# STM32_Rauch_001.net
KiCad netlist of a schematic drawn in EAGLE
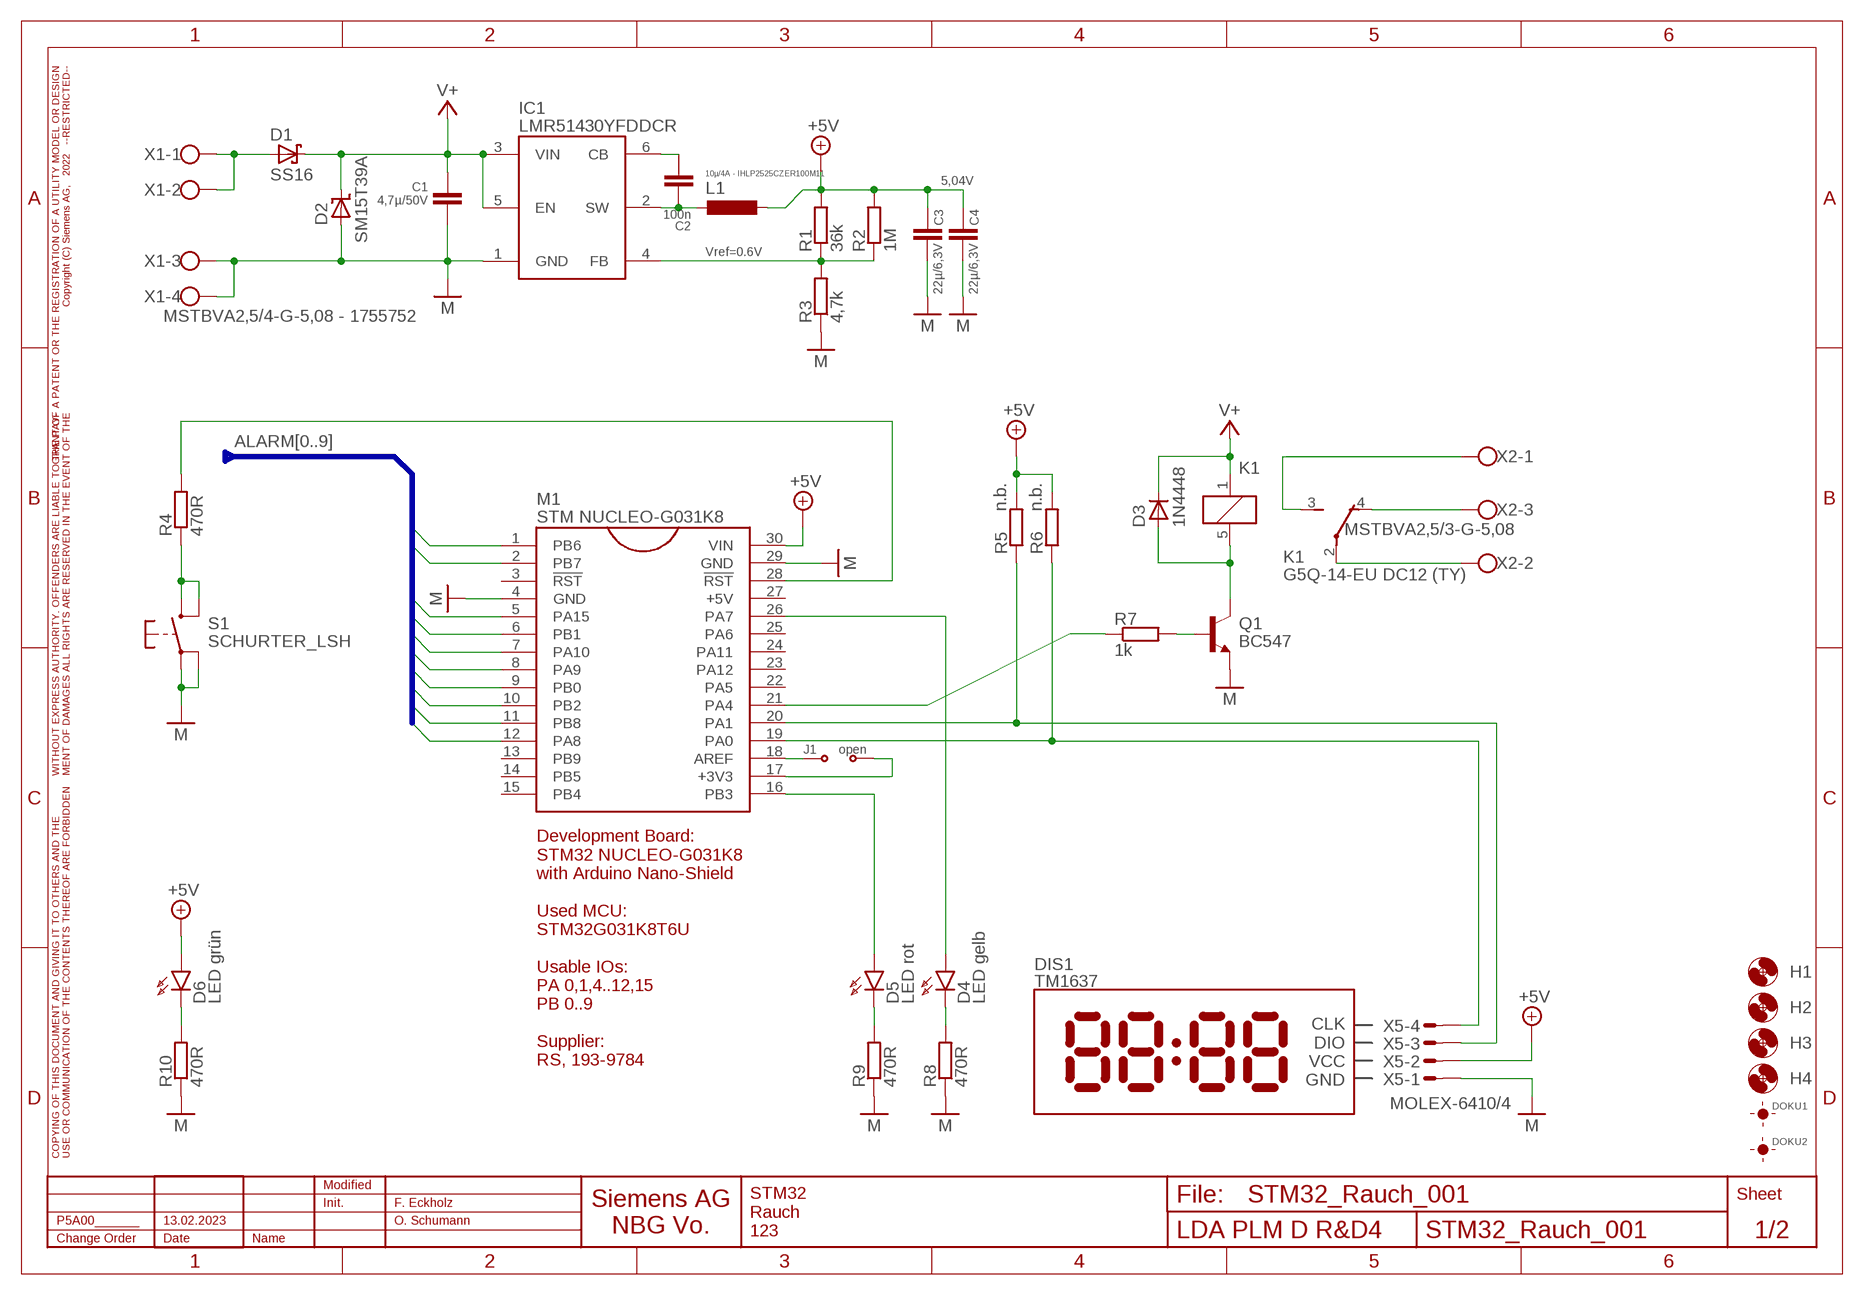
[diagram p0: schematic, sheet 1]
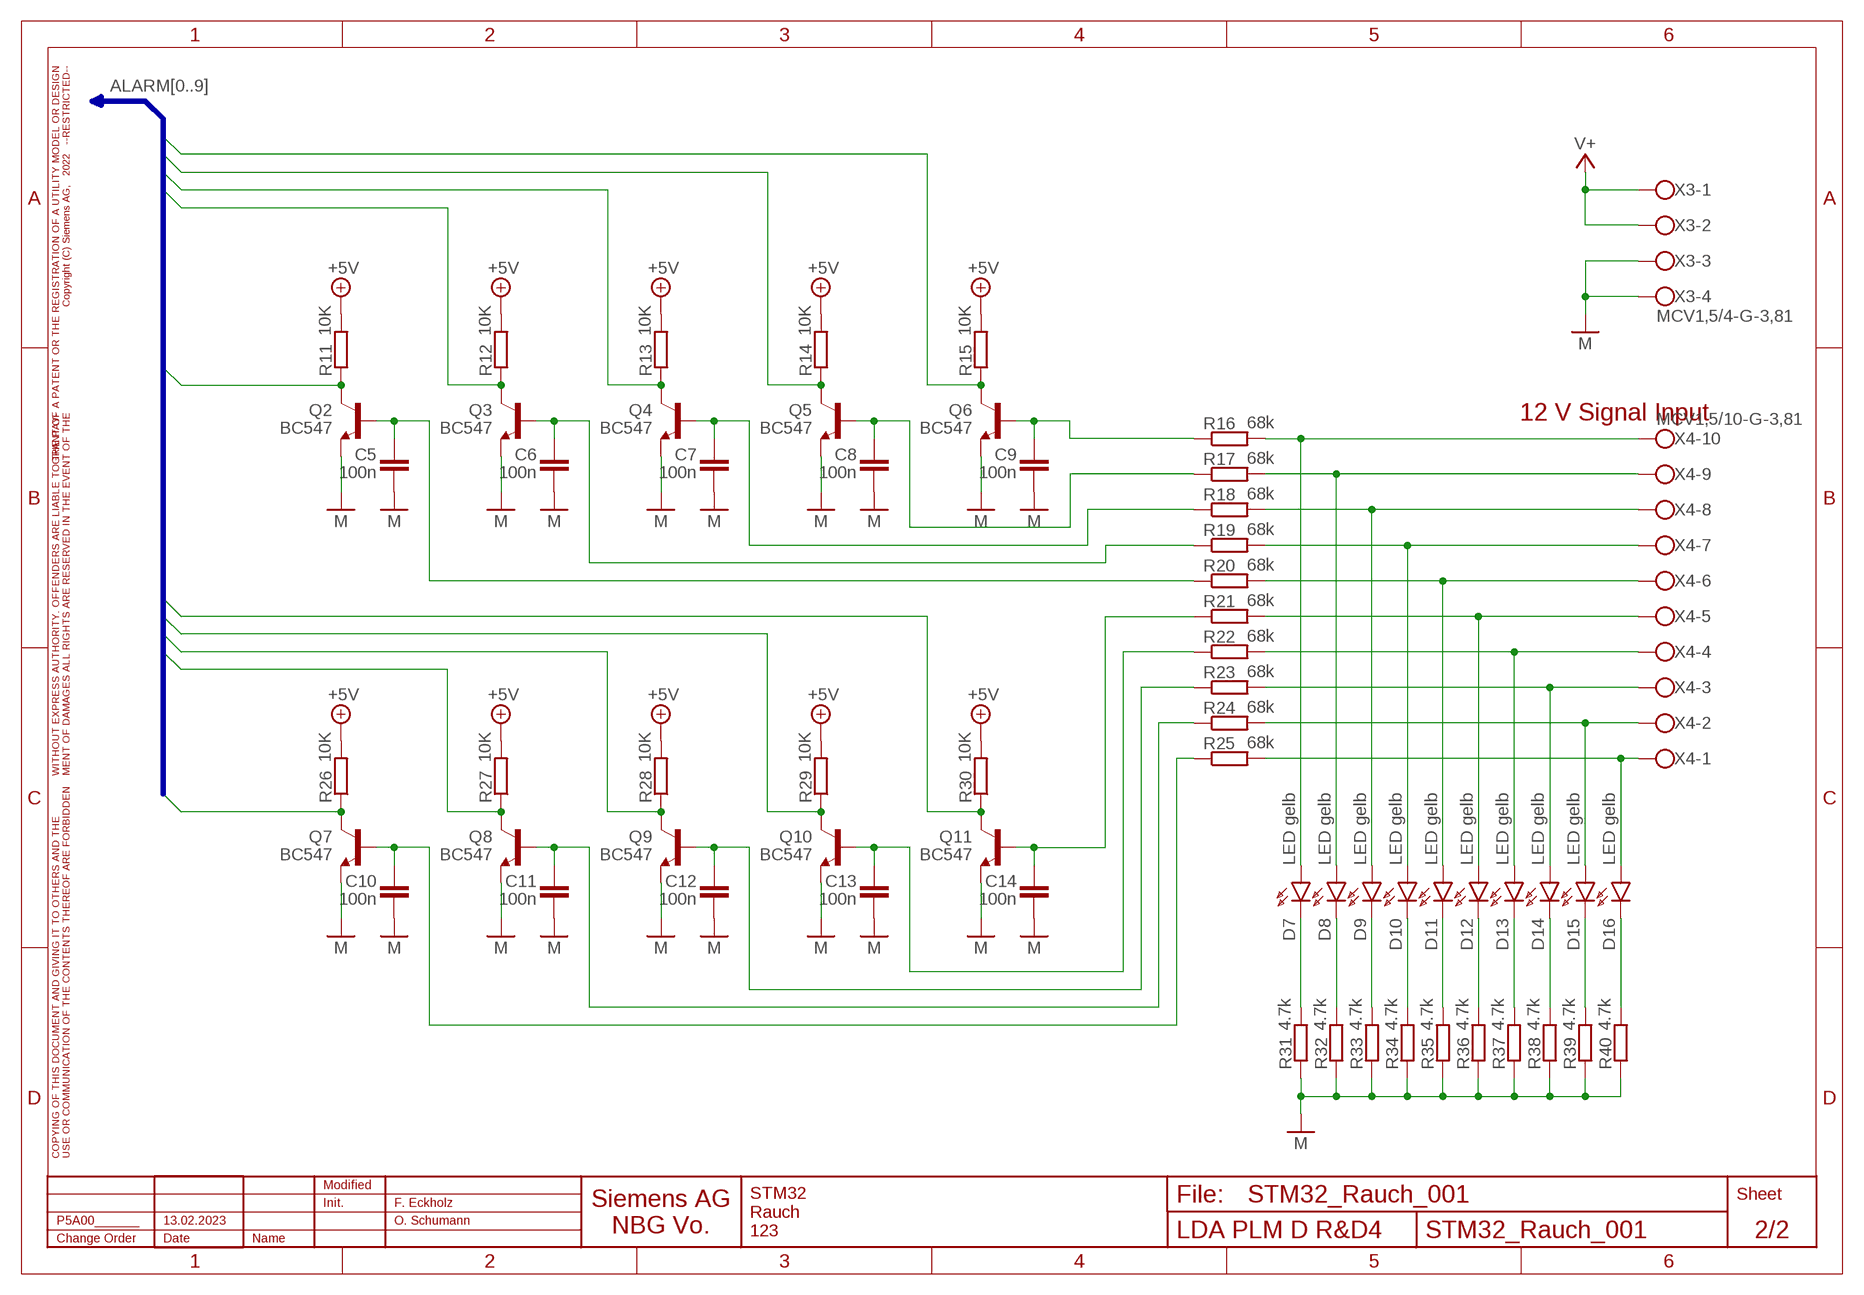
[diagram p1: schematic, sheet 2]

(export (version "E")
  (design (tool "Eeschema 10.0.6"))
  (components
    (comp (ref "C1")
      (value "4,7µ/50V")
      (footprint "eagle-import:CAPC1210")
      (libsource (lib "eagle-import") (part "C-EU1210"))
    )
    (comp (ref "C2")
      (value "100n")
      (footprint "eagle-import:CAPC0603")
      (libsource (lib "eagle-import") (part "C-EU0603"))
    )
    (comp (ref "C3")
      (value "22µ/6,3V")
      (footprint "eagle-import:CAPC1206")
      (libsource (lib "eagle-import") (part "C-EU1206"))
    )
    (comp (ref "C4")
      (value "22µ/6,3V")
      (footprint "eagle-import:CAPC1206")
      (libsource (lib "eagle-import") (part "C-EU1206"))
    )
    (comp (ref "D1")
      (value "SS16")
      (footprint "eagle-import:DIOM-SMA")
      (libsource (lib "eagle-import") (part "DIODE-SCHOTTKY-SMA"))
    )
    (comp (ref "D2")
      (value "SM15T39A")
      (footprint "eagle-import:DIOM-SMC")
      (libsource (lib "eagle-import") (part "DIODE-TVS-UNI-SMC"))
    )
    (comp (ref "D3")
      (value "1N4448")
      (footprint "eagle-import:SOD323")
      (libsource (lib "eagle-import") (part "DIODE-SOD323"))
    )
    (comp (ref "D4")
      (value "LED gelb")
      (footprint "eagle-import:LEDC1608")
      (libsource (lib "eagle-import") (part "DIODE-LED-C1608"))
    )
    (comp (ref "D5")
      (value "LED rot")
      (footprint "eagle-import:LEDC1608")
      (libsource (lib "eagle-import") (part "DIODE-LED-C1608"))
    )
    (comp (ref "D6")
      (value "LED grün")
      (footprint "eagle-import:LEDC1608")
      (libsource (lib "eagle-import") (part "DIODE-LED-C1608"))
    )
    (comp (ref "DIS1")
      (value "TM1637")
      (footprint "eagle-import:TM1637")
      (libsource (lib "eagle-import") (part "TM1637"))
    )
    (comp (ref "DOKU1")
      (value "PAD-FIDU-R200")
      (footprint "eagle-import:FIDU_RUND-2MM")
      (libsource (lib "eagle-import") (part "PAD-FIDU-R200"))
    )
    (comp (ref "DOKU2")
      (value "PAD-FIDU-R200")
      (footprint "eagle-import:FIDU_RUND-2MM")
      (libsource (lib "eagle-import") (part "PAD-FIDU-R200"))
    )
    (comp (ref "DOKU4")
      (value "STM32_Rauch_001")
      (footprint "eagle-import:DOKU-50-TOP")
      (libsource (lib "eagle-import") (part "TEXT-50-TOP"))
    )
    (comp (ref "H1")
      (value "MOUNT-HOLE-3.2")
      (footprint "eagle-import:MOUNT-HOLE-3,2")
      (libsource (lib "eagle-import") (part "MOUNT-HOLE-3.2"))
    )
    (comp (ref "H2")
      (value "MOUNT-HOLE-3.2")
      (footprint "eagle-import:MOUNT-HOLE-3,2")
      (libsource (lib "eagle-import") (part "MOUNT-HOLE-3.2"))
    )
    (comp (ref "H3")
      (value "MOUNT-HOLE-3.2")
      (footprint "eagle-import:MOUNT-HOLE-3,2")
      (libsource (lib "eagle-import") (part "MOUNT-HOLE-3.2"))
    )
    (comp (ref "H4")
      (value "MOUNT-HOLE-3.2")
      (footprint "eagle-import:MOUNT-HOLE-3,2")
      (libsource (lib "eagle-import") (part "MOUNT-HOLE-3.2"))
    )
    (comp (ref "IC1")
      (value "LMR51430YFDDCR")
      (footprint "eagle-import:SOT23-6")
      (libsource (lib "eagle-import") (part "LMR51430"))
    )
    (comp (ref "J1")
      (value "open")
      (footprint "eagle-import:CON-SOLDERJUMPER")
      (libsource (lib "eagle-import") (part "CON-J2D"))
    )
    (comp (ref "K1")
      (value "G5Q-14-EU DC12 (TY)")
      (footprint "eagle-import:OMRON-G5Q")
      (libsource (lib "eagle-import") (part "RELAIS1-OMRON-G5Q"))
    )
    (comp (ref "L1")
      (value "10µ/4A - IHLP2525CZER100M11")
      (footprint "eagle-import:INDM0707")
      (libsource (lib "eagle-import") (part "L-EU0707"))
    )
    (comp (ref "M1")
      (value "STM NUCLEO-G031K8")
      (footprint "eagle-import:NUCLEO32")
      (libsource (lib "eagle-import") (part "STM32-NUCLEO32"))
    )
    (comp (ref "Q1")
      (value "BC547")
      (footprint "eagle-import:SOT23")
      (libsource (lib "eagle-import") (part "TRANSISTOR-NPN-SOT23"))
    )
    (comp (ref "R1")
      (value "36k")
      (footprint "eagle-import:RESC0603")
      (libsource (lib "eagle-import") (part "R-EU_0603"))
    )
    (comp (ref "R2")
      (value "1M")
      (footprint "eagle-import:RESC0603")
      (libsource (lib "eagle-import") (part "R-EU_0603"))
    )
    (comp (ref "R3")
      (value "4,7k")
      (footprint "eagle-import:RESC0603")
      (libsource (lib "eagle-import") (part "R-EU_0603"))
    )
    (comp (ref "R4")
      (value "470R")
      (footprint "eagle-import:RESC0603")
      (libsource (lib "eagle-import") (part "R-EU_0603"))
    )
    (comp (ref "R5")
      (value "n.b.")
      (footprint "eagle-import:RESC0603")
      (libsource (lib "eagle-import") (part "R-EU_0603"))
    )
    (comp (ref "R6")
      (value "n.b.")
      (footprint "eagle-import:RESC0603")
      (libsource (lib "eagle-import") (part "R-EU_0603"))
    )
    (comp (ref "R7")
      (value "1k")
      (footprint "eagle-import:RESC0603")
      (libsource (lib "eagle-import") (part "R-EU_0603"))
    )
    (comp (ref "R8")
      (value "470R")
      (footprint "eagle-import:RESC0603")
      (libsource (lib "eagle-import") (part "R-EU_0603"))
    )
    (comp (ref "R9")
      (value "470R")
      (footprint "eagle-import:RESC0603")
      (libsource (lib "eagle-import") (part "R-EU_0603"))
    )
    (comp (ref "R10")
      (value "470R")
      (footprint "eagle-import:RESC0603")
      (libsource (lib "eagle-import") (part "R-EU_0603"))
    )
    (comp (ref "S1")
      (value "SCHURTER_LSH")
      (footprint "eagle-import:SHURTER_LSH")
      (libsource (lib "eagle-import") (part "SCHURTER_LSH"))
    )
    (comp (ref "X1")
      (value "MSTBVA2,5/4-G-5,08 - 1755752")
      (footprint "eagle-import:MSTBVA2,5_4-G-5,08")
      (libsource (lib "eagle-import") (part "MSTBVA2,5/4-G-5,08"))
    )
    (comp (ref "X2")
      (value "MSTBVA2,5/3-G-5,08")
      (footprint "eagle-import:MSTBVA2,5_3-G-5,08")
      (libsource (lib "eagle-import") (part "MSTBVA2,5/3-G-5,08"))
    )
    (comp (ref "X5")
      (value "MOLEX-6410/4")
      (footprint "eagle-import:MOLEX-6410_4")
      (libsource (lib "eagle-import") (part "MOLEX-6410/4"))
    )
    (comp (ref "C5")
      (value "100n")
      (footprint "eagle-import:CAPC0603")
      (libsource (lib "eagle-import") (part "C-EU0603"))
    )
    (comp (ref "C6")
      (value "100n")
      (footprint "eagle-import:CAPC0603")
      (libsource (lib "eagle-import") (part "C-EU0603"))
    )
    (comp (ref "C7")
      (value "100n")
      (footprint "eagle-import:CAPC0603")
      (libsource (lib "eagle-import") (part "C-EU0603"))
    )
    (comp (ref "C8")
      (value "100n")
      (footprint "eagle-import:CAPC0603")
      (libsource (lib "eagle-import") (part "C-EU0603"))
    )
    (comp (ref "C9")
      (value "100n")
      (footprint "eagle-import:CAPC0603")
      (libsource (lib "eagle-import") (part "C-EU0603"))
    )
    (comp (ref "C10")
      (value "100n")
      (footprint "eagle-import:CAPC0603")
      (libsource (lib "eagle-import") (part "C-EU0603"))
    )
    (comp (ref "C11")
      (value "100n")
      (footprint "eagle-import:CAPC0603")
      (libsource (lib "eagle-import") (part "C-EU0603"))
    )
    (comp (ref "C12")
      (value "100n")
      (footprint "eagle-import:CAPC0603")
      (libsource (lib "eagle-import") (part "C-EU0603"))
    )
    (comp (ref "C13")
      (value "100n")
      (footprint "eagle-import:CAPC0603")
      (libsource (lib "eagle-import") (part "C-EU0603"))
    )
    (comp (ref "C14")
      (value "100n")
      (footprint "eagle-import:CAPC0603")
      (libsource (lib "eagle-import") (part "C-EU0603"))
    )
    (comp (ref "D7")
      (value "LED gelb")
      (footprint "eagle-import:LEDC1608")
      (libsource (lib "eagle-import") (part "DIODE-LED-C1608"))
    )
    (comp (ref "D8")
      (value "LED gelb")
      (footprint "eagle-import:LEDC1608")
      (libsource (lib "eagle-import") (part "DIODE-LED-C1608"))
    )
    (comp (ref "D9")
      (value "LED gelb")
      (footprint "eagle-import:LEDC1608")
      (libsource (lib "eagle-import") (part "DIODE-LED-C1608"))
    )
    (comp (ref "D10")
      (value "LED gelb")
      (footprint "eagle-import:LEDC1608")
      (libsource (lib "eagle-import") (part "DIODE-LED-C1608"))
    )
    (comp (ref "D11")
      (value "LED gelb")
      (footprint "eagle-import:LEDC1608")
      (libsource (lib "eagle-import") (part "DIODE-LED-C1608"))
    )
    (comp (ref "D12")
      (value "LED gelb")
      (footprint "eagle-import:LEDC1608")
      (libsource (lib "eagle-import") (part "DIODE-LED-C1608"))
    )
    (comp (ref "D13")
      (value "LED gelb")
      (footprint "eagle-import:LEDC1608")
      (libsource (lib "eagle-import") (part "DIODE-LED-C1608"))
    )
    (comp (ref "D14")
      (value "LED gelb")
      (footprint "eagle-import:LEDC1608")
      (libsource (lib "eagle-import") (part "DIODE-LED-C1608"))
    )
    (comp (ref "D15")
      (value "LED gelb")
      (footprint "eagle-import:LEDC1608")
      (libsource (lib "eagle-import") (part "DIODE-LED-C1608"))
    )
    (comp (ref "D16")
      (value "LED gelb")
      (footprint "eagle-import:LEDC1608")
      (libsource (lib "eagle-import") (part "DIODE-LED-C1608"))
    )
    (comp (ref "DOKU4")
      (value "STM32_Rauch_001")
      (footprint "eagle-import:DOKU-50-TOP")
      (libsource (lib "eagle-import") (part "TEXT-50-TOP"))
    )
    (comp (ref "Q2")
      (value "BC547")
      (footprint "eagle-import:SOT23")
      (libsource (lib "eagle-import") (part "TRANSISTOR-NPN-SOT23"))
    )
    (comp (ref "Q3")
      (value "BC547")
      (footprint "eagle-import:SOT23")
      (libsource (lib "eagle-import") (part "TRANSISTOR-NPN-SOT23"))
    )
    (comp (ref "Q4")
      (value "BC547")
      (footprint "eagle-import:SOT23")
      (libsource (lib "eagle-import") (part "TRANSISTOR-NPN-SOT23"))
    )
    (comp (ref "Q5")
      (value "BC547")
      (footprint "eagle-import:SOT23")
      (libsource (lib "eagle-import") (part "TRANSISTOR-NPN-SOT23"))
    )
    (comp (ref "Q6")
      (value "BC547")
      (footprint "eagle-import:SOT23")
      (libsource (lib "eagle-import") (part "TRANSISTOR-NPN-SOT23"))
    )
    (comp (ref "Q7")
      (value "BC547")
      (footprint "eagle-import:SOT23")
      (libsource (lib "eagle-import") (part "TRANSISTOR-NPN-SOT23"))
    )
    (comp (ref "Q8")
      (value "BC547")
      (footprint "eagle-import:SOT23")
      (libsource (lib "eagle-import") (part "TRANSISTOR-NPN-SOT23"))
    )
    (comp (ref "Q9")
      (value "BC547")
      (footprint "eagle-import:SOT23")
      (libsource (lib "eagle-import") (part "TRANSISTOR-NPN-SOT23"))
    )
    (comp (ref "Q10")
      (value "BC547")
      (footprint "eagle-import:SOT23")
      (libsource (lib "eagle-import") (part "TRANSISTOR-NPN-SOT23"))
    )
    (comp (ref "Q11")
      (value "BC547")
      (footprint "eagle-import:SOT23")
      (libsource (lib "eagle-import") (part "TRANSISTOR-NPN-SOT23"))
    )
    (comp (ref "R11")
      (value "10K")
      (footprint "eagle-import:RESC0603")
      (libsource (lib "eagle-import") (part "R-EU_0603"))
    )
    (comp (ref "R12")
      (value "10K")
      (footprint "eagle-import:RESC0603")
      (libsource (lib "eagle-import") (part "R-EU_0603"))
    )
    (comp (ref "R13")
      (value "10K")
      (footprint "eagle-import:RESC0603")
      (libsource (lib "eagle-import") (part "R-EU_0603"))
    )
    (comp (ref "R14")
      (value "10K")
      (footprint "eagle-import:RESC0603")
      (libsource (lib "eagle-import") (part "R-EU_0603"))
    )
    (comp (ref "R15")
      (value "10K")
      (footprint "eagle-import:RESC0603")
      (libsource (lib "eagle-import") (part "R-EU_0603"))
    )
    (comp (ref "R16")
      (value "68k")
      (footprint "eagle-import:RESC0603")
      (libsource (lib "eagle-import") (part "R-EU_0603"))
    )
    (comp (ref "R17")
      (value "68k")
      (footprint "eagle-import:RESC0603")
      (libsource (lib "eagle-import") (part "R-EU_0603"))
    )
    (comp (ref "R18")
      (value "68k")
      (footprint "eagle-import:RESC0603")
      (libsource (lib "eagle-import") (part "R-EU_0603"))
    )
    (comp (ref "R19")
      (value "68k")
      (footprint "eagle-import:RESC0603")
      (libsource (lib "eagle-import") (part "R-EU_0603"))
    )
    (comp (ref "R20")
      (value "68k")
      (footprint "eagle-import:RESC0603")
      (libsource (lib "eagle-import") (part "R-EU_0603"))
    )
    (comp (ref "R21")
      (value "68k")
      (footprint "eagle-import:RESC0603")
      (libsource (lib "eagle-import") (part "R-EU_0603"))
    )
    (comp (ref "R22")
      (value "68k")
      (footprint "eagle-import:RESC0603")
      (libsource (lib "eagle-import") (part "R-EU_0603"))
    )
    (comp (ref "R23")
      (value "68k")
      (footprint "eagle-import:RESC0603")
      (libsource (lib "eagle-import") (part "R-EU_0603"))
    )
    (comp (ref "R24")
      (value "68k")
      (footprint "eagle-import:RESC0603")
      (libsource (lib "eagle-import") (part "R-EU_0603"))
    )
    (comp (ref "R25")
      (value "68k")
      (footprint "eagle-import:RESC0603")
      (libsource (lib "eagle-import") (part "R-EU_0603"))
    )
    (comp (ref "R26")
      (value "10K")
      (footprint "eagle-import:RESC0603")
      (libsource (lib "eagle-import") (part "R-EU_0603"))
    )
    (comp (ref "R27")
      (value "10K")
      (footprint "eagle-import:RESC0603")
      (libsource (lib "eagle-import") (part "R-EU_0603"))
    )
    (comp (ref "R28")
      (value "10K")
      (footprint "eagle-import:RESC0603")
      (libsource (lib "eagle-import") (part "R-EU_0603"))
    )
    (comp (ref "R29")
      (value "10K")
      (footprint "eagle-import:RESC0603")
      (libsource (lib "eagle-import") (part "R-EU_0603"))
    )
    (comp (ref "R30")
      (value "10K")
      (footprint "eagle-import:RESC0603")
      (libsource (lib "eagle-import") (part "R-EU_0603"))
    )
    (comp (ref "R31")
      (value "4.7k")
      (footprint "eagle-import:RESC0603")
      (libsource (lib "eagle-import") (part "R-EU_0603"))
    )
    (comp (ref "R32")
      (value "4.7k")
      (footprint "eagle-import:RESC0603")
      (libsource (lib "eagle-import") (part "R-EU_0603"))
    )
    (comp (ref "R33")
      (value "4.7k")
      (footprint "eagle-import:RESC0603")
      (libsource (lib "eagle-import") (part "R-EU_0603"))
    )
    (comp (ref "R34")
      (value "4.7k")
      (footprint "eagle-import:RESC0603")
      (libsource (lib "eagle-import") (part "R-EU_0603"))
    )
    (comp (ref "R35")
      (value "4.7k")
      (footprint "eagle-import:RESC0603")
      (libsource (lib "eagle-import") (part "R-EU_0603"))
    )
    (comp (ref "R36")
      (value "4.7k")
      (footprint "eagle-import:RESC0603")
      (libsource (lib "eagle-import") (part "R-EU_0603"))
    )
    (comp (ref "R37")
      (value "4.7k")
      (footprint "eagle-import:RESC0603")
      (libsource (lib "eagle-import") (part "R-EU_0603"))
    )
    (comp (ref "R38")
      (value "4.7k")
      (footprint "eagle-import:RESC0603")
      (libsource (lib "eagle-import") (part "R-EU_0603"))
    )
    (comp (ref "R39")
      (value "4.7k")
      (footprint "eagle-import:RESC0603")
      (libsource (lib "eagle-import") (part "R-EU_0603"))
    )
    (comp (ref "R40")
      (value "4.7k")
      (footprint "eagle-import:RESC0603")
      (libsource (lib "eagle-import") (part "R-EU_0603"))
    )
    (comp (ref "X3")
      (value "MCV1,5/4-G-3,81")
      (footprint "eagle-import:MCV1,5_4-G-3,81")
      (libsource (lib "eagle-import") (part "MCV1,5/4-G-3,81"))
    )
    (comp (ref "X4")
      (value "MCV1,5/10-G-3,81")
      (footprint "eagle-import:MCV1,5_10-G-3,81")
      (libsource (lib "eagle-import") (part "MCV1,5/10-G-3,81"))
    )
  )
  (nets
    (net (code "1") (name "+5V") (class "Default")
      (node (ref "C3") (pin "2") (pinfunction "2_2") (pintype "passive"))
      (node (ref "C4") (pin "2") (pinfunction "2_2") (pintype "passive"))
      (node (ref "D6") (pin "2") (pinfunction "A_2") (pintype "passive"))
      (node (ref "L1") (pin "2") (pinfunction "2_2") (pintype "passive"))
      (node (ref "M1") (pin "30") (pinfunction "VIN_30") (pintype "passive"))
      (node (ref "R1") (pin "2") (pinfunction "2_2") (pintype "passive"))
      (node (ref "R11") (pin "2") (pinfunction "2_2") (pintype "passive"))
      (node (ref "R12") (pin "2") (pinfunction "2_2") (pintype "passive"))
      (node (ref "R13") (pin "2") (pinfunction "2_2") (pintype "passive"))
      (node (ref "R14") (pin "2") (pinfunction "2_2") (pintype "passive"))
      (node (ref "R15") (pin "2") (pinfunction "2_2") (pintype "passive"))
      (node (ref "R2") (pin "2") (pinfunction "2_2") (pintype "passive"))
      (node (ref "R26") (pin "2") (pinfunction "2_2") (pintype "passive"))
      (node (ref "R27") (pin "2") (pinfunction "2_2") (pintype "passive"))
      (node (ref "R28") (pin "2") (pinfunction "2_2") (pintype "passive"))
      (node (ref "R29") (pin "2") (pinfunction "2_2") (pintype "passive"))
      (node (ref "R30") (pin "2") (pinfunction "2_2") (pintype "passive"))
      (node (ref "R5") (pin "2") (pinfunction "2_2") (pintype "passive"))
      (node (ref "R6") (pin "2") (pinfunction "2_2") (pintype "passive"))
      (node (ref "X5") (pin "2") (pinfunction "S_2") (pintype "passive"))
    )
    (net (code "4") (name "ALARM0") (class "Default")
      (node (ref "M1") (pin "1") (pinfunction "PB6_1") (pintype "bidirectional"))
      (node (ref "Q6") (pin "3") (pinfunction "C_3") (pintype "passive"))
      (node (ref "R15") (pin "1") (pinfunction "1_1") (pintype "passive"))
    )
    (net (code "5") (name "ALARM1") (class "Default")
      (node (ref "M1") (pin "2") (pinfunction "PB7_2") (pintype "bidirectional"))
      (node (ref "Q5") (pin "3") (pinfunction "C_3") (pintype "passive"))
      (node (ref "R14") (pin "1") (pinfunction "1_1") (pintype "passive"))
    )
    (net (code "6") (name "ALARM2") (class "Default")
      (node (ref "M1") (pin "5") (pinfunction "PA15_5") (pintype "bidirectional"))
      (node (ref "Q4") (pin "3") (pinfunction "C_3") (pintype "passive"))
      (node (ref "R13") (pin "1") (pinfunction "1_1") (pintype "passive"))
    )
    (net (code "7") (name "ALARM3") (class "Default")
      (node (ref "M1") (pin "6") (pinfunction "PB1_6") (pintype "bidirectional"))
      (node (ref "Q3") (pin "3") (pinfunction "C_3") (pintype "passive"))
      (node (ref "R12") (pin "1") (pinfunction "1_1") (pintype "passive"))
    )
    (net (code "8") (name "ALARM4") (class "Default")
      (node (ref "M1") (pin "7") (pinfunction "PA10_7") (pintype "bidirectional"))
      (node (ref "Q2") (pin "3") (pinfunction "C_3") (pintype "passive"))
      (node (ref "R11") (pin "1") (pinfunction "1_1") (pintype "passive"))
    )
    (net (code "9") (name "ALARM5") (class "Default")
      (node (ref "M1") (pin "8") (pinfunction "PA9_8") (pintype "bidirectional"))
      (node (ref "Q11") (pin "3") (pinfunction "C_3") (pintype "passive"))
      (node (ref "R30") (pin "1") (pinfunction "1_1") (pintype "passive"))
    )
    (net (code "10") (name "ALARM6") (class "Default")
      (node (ref "M1") (pin "9") (pinfunction "PB0_9") (pintype "bidirectional"))
      (node (ref "Q10") (pin "3") (pinfunction "C_3") (pintype "passive"))
      (node (ref "R29") (pin "1") (pinfunction "1_1") (pintype "passive"))
    )
    (net (code "11") (name "ALARM7") (class "Default")
      (node (ref "M1") (pin "10") (pinfunction "PB2_10") (pintype "bidirectional"))
      (node (ref "Q9") (pin "3") (pinfunction "C_3") (pintype "passive"))
      (node (ref "R28") (pin "1") (pinfunction "1_1") (pintype "passive"))
    )
    (net (code "12") (name "ALARM8") (class "Default")
      (node (ref "M1") (pin "11") (pinfunction "PB8_11") (pintype "bidirectional"))
      (node (ref "Q8") (pin "3") (pinfunction "C_3") (pintype "passive"))
      (node (ref "R27") (pin "1") (pinfunction "1_1") (pintype "passive"))
    )
    (net (code "13") (name "ALARM9") (class "Default")
      (node (ref "M1") (pin "12") (pinfunction "PA8_12") (pintype "bidirectional"))
      (node (ref "Q7") (pin "3") (pinfunction "C_3") (pintype "passive"))
      (node (ref "R26") (pin "1") (pinfunction "1_1") (pintype "passive"))
    )
    (net (code "14") (name "M") (class "Default")
      (node (ref "C1") (pin "1") (pinfunction "1_1") (pintype "passive"))
      (node (ref "C10") (pin "1") (pinfunction "1_1") (pintype "passive"))
      (node (ref "C11") (pin "1") (pinfunction "1_1") (pintype "passive"))
      (node (ref "C12") (pin "1") (pinfunction "1_1") (pintype "passive"))
      (node (ref "C13") (pin "1") (pinfunction "1_1") (pintype "passive"))
      (node (ref "C14") (pin "1") (pinfunction "1_1") (pintype "passive"))
      (node (ref "C3") (pin "1") (pinfunction "1_1") (pintype "passive"))
      (node (ref "C4") (pin "1") (pinfunction "1_1") (pintype "passive"))
      (node (ref "C5") (pin "1") (pinfunction "1_1") (pintype "passive"))
      (node (ref "C6") (pin "1") (pinfunction "1_1") (pintype "passive"))
      (node (ref "C7") (pin "1") (pinfunction "1_1") (pintype "passive"))
      (node (ref "C8") (pin "1") (pinfunction "1_1") (pintype "passive"))
      (node (ref "C9") (pin "1") (pinfunction "1_1") (pintype "passive"))
      (node (ref "D2") (pin "2") (pinfunction "A_2") (pintype "passive"))
      (node (ref "IC1") (pin "1") (pinfunction "GND_1") (pintype "power_in"))
      (node (ref "M1") (pin "29") (pinfunction "GND_29") (pintype "passive"))
      (node (ref "M1") (pin "4") (pinfunction "GND_4") (pintype "passive"))
      (node (ref "Q1") (pin "2") (pinfunction "E_2") (pintype "passive"))
      (node (ref "Q10") (pin "2") (pinfunction "E_2") (pintype "passive"))
      (node (ref "Q11") (pin "2") (pinfunction "E_2") (pintype "passive"))
      (node (ref "Q2") (pin "2") (pinfunction "E_2") (pintype "passive"))
      (node (ref "Q3") (pin "2") (pinfunction "E_2") (pintype "passive"))
      (node (ref "Q4") (pin "2") (pinfunction "E_2") (pintype "passive"))
      (node (ref "Q5") (pin "2") (pinfunction "E_2") (pintype "passive"))
      (node (ref "Q6") (pin "2") (pinfunction "E_2") (pintype "passive"))
      (node (ref "Q7") (pin "2") (pinfunction "E_2") (pintype "passive"))
      (node (ref "Q8") (pin "2") (pinfunction "E_2") (pintype "passive"))
      (node (ref "Q9") (pin "2") (pinfunction "E_2") (pintype "passive"))
      (node (ref "R10") (pin "1") (pinfunction "1_1") (pintype "passive"))
      (node (ref "R3") (pin "1") (pinfunction "1_1") (pintype "passive"))
      (node (ref "R31") (pin "1") (pinfunction "1_1") (pintype "passive"))
      (node (ref "R32") (pin "1") (pinfunction "1_1") (pintype "passive"))
      (node (ref "R33") (pin "1") (pinfunction "1_1") (pintype "passive"))
      (node (ref "R34") (pin "1") (pinfunction "1_1") (pintype "passive"))
      (node (ref "R35") (pin "1") (pinfunction "1_1") (pintype "passive"))
      (node (ref "R36") (pin "1") (pinfunction "1_1") (pintype "passive"))
      (node (ref "R37") (pin "1") (pinfunction "1_1") (pintype "passive"))
      (node (ref "R38") (pin "1") (pinfunction "1_1") (pintype "passive"))
      (node (ref "R39") (pin "1") (pinfunction "1_1") (pintype "passive"))
      (node (ref "R40") (pin "1") (pinfunction "1_1") (pintype "passive"))
      (node (ref "R8") (pin "1") (pinfunction "1_1") (pintype "passive"))
      (node (ref "R9") (pin "1") (pinfunction "1_1") (pintype "passive"))
      (node (ref "S1") (pin "1") (pinfunction "P_1") (pintype "passive"))
      (node (ref "S1") (pin "2") (pinfunction "P_2") (pintype "passive"))
      (node (ref "X1") (pin "3") (pinfunction "KL_3") (pintype "passive"))
      (node (ref "X1") (pin "4") (pinfunction "KL_4") (pintype "passive"))
      (node (ref "X3") (pin "P$3") (pinfunction "KL_P$3") (pintype "passive"))
      (node (ref "X3") (pin "P$4") (pinfunction "KL_P$4") (pintype "passive"))
      (node (ref "X5") (pin "1") (pinfunction "S_1") (pintype "passive"))
    )
    (net (code "15") (name "Net-(D1-A)") (class "Default")
      (node (ref "D1") (pin "2") (pinfunction "A_2") (pintype "passive"))
      (node (ref "X1") (pin "1") (pinfunction "KL_1") (pintype "passive"))
      (node (ref "X1") (pin "2") (pinfunction "KL_2") (pintype "passive"))
    )
    (net (code "16") (name "Net-(D4-A)") (class "Default")
      (node (ref "D4") (pin "2") (pinfunction "A_2") (pintype "passive"))
      (node (ref "M1") (pin "26") (pinfunction "PA7_26") (pintype "bidirectional"))
    )
    (net (code "17") (name "Net-(D4-C)") (class "Default")
      (node (ref "D4") (pin "1") (pinfunction "C_1") (pintype "passive"))
      (node (ref "R8") (pin "2") (pinfunction "2_2") (pintype "passive"))
    )
    (net (code "18") (name "Net-(D5-A)") (class "Default")
      (node (ref "D5") (pin "2") (pinfunction "A_2") (pintype "passive"))
      (node (ref "M1") (pin "16") (pinfunction "PB3_16") (pintype "bidirectional"))
    )
    (net (code "19") (name "Net-(D5-C)") (class "Default")
      (node (ref "D5") (pin "1") (pinfunction "C_1") (pintype "passive"))
      (node (ref "R9") (pin "2") (pinfunction "2_2") (pintype "passive"))
    )
    (net (code "20") (name "Net-(D6-C)") (class "Default")
      (node (ref "D6") (pin "1") (pinfunction "C_1") (pintype "passive"))
      (node (ref "R10") (pin "2") (pinfunction "2_2") (pintype "passive"))
    )
    (net (code "21") (name "Net-(D7-A)") (class "Default")
      (node (ref "D7") (pin "2") (pinfunction "A_2") (pintype "passive"))
      (node (ref "R16") (pin "2") (pinfunction "2_2") (pintype "passive"))
      (node (ref "X4") (pin "P$10") (pinfunction "KL_P$10") (pintype "passive"))
    )
    (net (code "22") (name "Net-(D7-C)") (class "Default")
      (node (ref "D7") (pin "1") (pinfunction "C_1") (pintype "passive"))
      (node (ref "R31") (pin "2") (pinfunction "2_2") (pintype "passive"))
    )
    (net (code "23") (name "Net-(D8-A)") (class "Default")
      (node (ref "D8") (pin "2") (pinfunction "A_2") (pintype "passive"))
      (node (ref "R17") (pin "2") (pinfunction "2_2") (pintype "passive"))
      (node (ref "X4") (pin "P$9") (pinfunction "KL_P$9") (pintype "passive"))
    )
    (net (code "24") (name "Net-(D8-C)") (class "Default")
      (node (ref "D8") (pin "1") (pinfunction "C_1") (pintype "passive"))
      (node (ref "R32") (pin "2") (pinfunction "2_2") (pintype "passive"))
    )
    (net (code "25") (name "Net-(D9-A)") (class "Default")
      (node (ref "D9") (pin "2") (pinfunction "A_2") (pintype "passive"))
      (node (ref "R18") (pin "2") (pinfunction "2_2") (pintype "passive"))
      (node (ref "X4") (pin "P$8") (pinfunction "KL_P$8") (pintype "passive"))
    )
    (net (code "26") (name "Net-(D9-C)") (class "Default")
      (node (ref "D9") (pin "1") (pinfunction "C_1") (pintype "passive"))
      (node (ref "R33") (pin "2") (pinfunction "2_2") (pintype "passive"))
    )
    (net (code "27") (name "Net-(D10-A)") (class "Default")
      (node (ref "D10") (pin "2") (pinfunction "A_2") (pintype "passive"))
      (node (ref "R19") (pin "2") (pinfunction "2_2") (pintype "passive"))
      (node (ref "X4") (pin "P$7") (pinfunction "KL_P$7") (pintype "passive"))
    )
    (net (code "28") (name "Net-(D10-C)") (class "Default")
      (node (ref "D10") (pin "1") (pinfunction "C_1") (pintype "passive"))
      (node (ref "R34") (pin "2") (pinfunction "2_2") (pintype "passive"))
    )
    (net (code "29") (name "Net-(D11-A)") (class "Default")
      (node (ref "D11") (pin "2") (pinfunction "A_2") (pintype "passive"))
      (node (ref "R20") (pin "2") (pinfunction "2_2") (pintype "passive"))
      (node (ref "X4") (pin "P$6") (pinfunction "KL_P$6") (pintype "passive"))
    )
    (net (code "30") (name "Net-(D11-C)") (class "Default")
      (node (ref "D11") (pin "1") (pinfunction "C_1") (pintype "passive"))
      (node (ref "R35") (pin "2") (pinfunction "2_2") (pintype "passive"))
    )
    (net (code "31") (name "Net-(D12-A)") (class "Default")
      (node (ref "D12") (pin "2") (pinfunction "A_2") (pintype "passive"))
      (node (ref "R21") (pin "2") (pinfunction "2_2") (pintype "passive"))
      (node (ref "X4") (pin "P$5") (pinfunction "KL_P$5") (pintype "passive"))
    )
    (net (code "32") (name "Net-(D12-C)") (class "Default")
      (node (ref "D12") (pin "1") (pinfunction "C_1") (pintype "passive"))
      (node (ref "R36") (pin "2") (pinfunction "2_2") (pintype "passive"))
    )
    (net (code "33") (name "Net-(D13-A)") (class "Default")
      (node (ref "D13") (pin "2") (pinfunction "A_2") (pintype "passive"))
      (node (ref "R22") (pin "2") (pinfunction "2_2") (pintype "passive"))
      (node (ref "X4") (pin "P$4") (pinfunction "KL_P$4") (pintype "passive"))
    )
    (net (code "34") (name "Net-(D13-C)") (class "Default")
      (node (ref "D13") (pin "1") (pinfunction "C_1") (pintype "passive"))
      (node (ref "R37") (pin "2") (pinfunction "2_2") (pintype "passive"))
    )
    (net (code "35") (name "Net-(D14-A)") (class "Default")
      (node (ref "D14") (pin "2") (pinfunction "A_2") (pintype "passive"))
      (node (ref "R23") (pin "2") (pinfunction "2_2") (pintype "passive"))
      (node (ref "X4") (pin "P$3") (pinfunction "KL_P$3") (pintype "passive"))
    )
    (net (code "36") (name "Net-(D14-C)") (class "Default")
      (node (ref "D14") (pin "1") (pinfunction "C_1") (pintype "passive"))
      (node (ref "R38") (pin "2") (pinfunction "2_2") (pintype "passive"))
    )
    (net (code "37") (name "Net-(D15-A)") (class "Default")
      (node (ref "D15") (pin "2") (pinfunction "A_2") (pintype "passive"))
      (node (ref "R24") (pin "2") (pinfunction "2_2") (pintype "passive"))
      (node (ref "X4") (pin "P$2") (pinfunction "KL_P$2") (pintype "passive"))
    )
    (net (code "38") (name "Net-(D15-C)") (class "Default")
      (node (ref "D15") (pin "1") (pinfunction "C_1") (pintype "passive"))
      (node (ref "R39") (pin "2") (pinfunction "2_2") (pintype "passive"))
    )
    (net (code "39") (name "Net-(D16-A)") (class "Default")
      (node (ref "D16") (pin "2") (pinfunction "A_2") (pintype "passive"))
      (node (ref "R25") (pin "2") (pinfunction "2_2") (pintype "passive"))
      (node (ref "X4") (pin "P$1") (pinfunction "KL_P$1") (pintype "passive"))
    )
    (net (code "40") (name "Net-(D16-C)") (class "Default")
      (node (ref "D16") (pin "1") (pinfunction "C_1") (pintype "passive"))
      (node (ref "R40") (pin "2") (pinfunction "2_2") (pintype "passive"))
    )
    (net (code "41") (name "Net-(IC1-CB)") (class "Default")
      (node (ref "C2") (pin "1") (pinfunction "1_1") (pintype "passive"))
      (node (ref "IC1") (pin "6") (pinfunction "CB_6") (pintype "input"))
    )
    (net (code "42") (name "Net-(IC1-FB)") (class "Default")
      (node (ref "IC1") (pin "4") (pinfunction "FB_4") (pintype "input"))
      (node (ref "R1") (pin "1") (pinfunction "1_1") (pintype "passive"))
      (node (ref "R2") (pin "1") (pinfunction "1_1") (pintype "passive"))
      (node (ref "R3") (pin "2") (pinfunction "2_2") (pintype "passive"))
    )
    (net (code "43") (name "Net-(IC1-SW)") (class "Default")
      (node (ref "C2") (pin "2") (pinfunction "2_2") (pintype "passive"))
      (node (ref "IC1") (pin "2") (pinfunction "SW_2") (pintype "output"))
      (node (ref "L1") (pin "1") (pinfunction "1_1") (pintype "passive"))
    )
    (net (code "44") (name "Net-(K1A-COIL2)") (class "Default")
      (node (ref "D3") (pin "A") (pinfunction "A_A") (pintype "passive"))
      (node (ref "K1") (pin "5") (pinfunction "COIL2_5") (pintype "passive"))
      (node (ref "Q1") (pin "3") (pinfunction "C_3") (pintype "passive"))
    )
    (net (code "45") (name "Net-(K1B-C)") (class "Default")
      (node (ref "K1") (pin "2") (pinfunction "C_2") (pintype "passive"))
      (node (ref "X2") (pin "2") (pinfunction "KL_2") (pintype "passive"))
    )
    (net (code "46") (name "Net-(K1B-NC)") (class "Default")
      (node (ref "K1") (pin "4") (pinfunction "NC_4") (pintype "passive"))
      (node (ref "X2") (pin "3") (pinfunction "KL_3") (pintype "passive"))
    )
    (net (code "47") (name "Net-(K1B-NO)") (class "Default")
      (node (ref "K1") (pin "3") (pinfunction "NO_3") (pintype "passive"))
      (node (ref "X2") (pin "1") (pinfunction "KL_1") (pintype "passive"))
    )
    (net (code "48") (name "Net-(M1-+3V3)") (class "Default")
      (node (ref "J1") (pin "2") (pinfunction "2_2") (pintype "bidirectional"))
      (node (ref "M1") (pin "17") (pinfunction "+3V3_17") (pintype "passive"))
    )
    (net (code "49") (name "Net-(M1-AREF)") (class "Default")
      (node (ref "J1") (pin "1") (pinfunction "1_1") (pintype "bidirectional"))
      (node (ref "M1") (pin "18") (pinfunction "AREF_18") (pintype "passive"))
    )
    (net (code "50") (name "Net-(M1-PA0)") (class "Default")
      (node (ref "M1") (pin "19") (pinfunction "PA0_19") (pintype "bidirectional"))
      (node (ref "R6") (pin "1") (pinfunction "1_1") (pintype "passive"))
      (node (ref "X5") (pin "4") (pinfunction "S_4") (pintype "passive"))
    )
    (net (code "51") (name "Net-(M1-PA1)") (class "Default")
      (node (ref "M1") (pin "20") (pinfunction "PA1_20") (pintype "bidirectional"))
      (node (ref "R5") (pin "1") (pinfunction "1_1") (pintype "passive"))
      (node (ref "X5") (pin "3") (pinfunction "S_3") (pintype "passive"))
    )
    (net (code "52") (name "Net-(M1-PA4)") (class "Default")
      (node (ref "M1") (pin "21") (pinfunction "PA4_21") (pintype "bidirectional"))
      (node (ref "R7") (pin "1") (pinfunction "1_1") (pintype "passive"))
    )
    (net (code "53") (name "Net-(M1-~{RST}-Pad28)") (class "Default")
      (node (ref "M1") (pin "28") (pinfunction "~{RST}_28") (pintype "input"))
      (node (ref "R4") (pin "2") (pinfunction "2_2") (pintype "passive"))
    )
    (net (code "54") (name "Net-(Q1-B)") (class "Default")
      (node (ref "Q1") (pin "1") (pinfunction "B_1") (pintype "passive"))
      (node (ref "R7") (pin "2") (pinfunction "2_2") (pintype "passive"))
    )
    (net (code "55") (name "Net-(Q2-B)") (class "Default")
      (node (ref "C5") (pin "2") (pinfunction "2_2") (pintype "passive"))
      (node (ref "Q2") (pin "1") (pinfunction "B_1") (pintype "passive"))
      (node (ref "R20") (pin "1") (pinfunction "1_1") (pintype "passive"))
    )
    (net (code "56") (name "Net-(Q3-B)") (class "Default")
      (node (ref "C6") (pin "2") (pinfunction "2_2") (pintype "passive"))
      (node (ref "Q3") (pin "1") (pinfunction "B_1") (pintype "passive"))
      (node (ref "R19") (pin "1") (pinfunction "1_1") (pintype "passive"))
    )
    (net (code "57") (name "Net-(Q4-B)") (class "Default")
      (node (ref "C7") (pin "2") (pinfunction "2_2") (pintype "passive"))
      (node (ref "Q4") (pin "1") (pinfunction "B_1") (pintype "passive"))
      (node (ref "R18") (pin "1") (pinfunction "1_1") (pintype "passive"))
    )
    (net (code "58") (name "Net-(Q5-B)") (class "Default")
      (node (ref "C8") (pin "2") (pinfunction "2_2") (pintype "passive"))
      (node (ref "Q5") (pin "1") (pinfunction "B_1") (pintype "passive"))
      (node (ref "R17") (pin "1") (pinfunction "1_1") (pintype "passive"))
    )
    (net (code "59") (name "Net-(Q6-B)") (class "Default")
      (node (ref "C9") (pin "2") (pinfunction "2_2") (pintype "passive"))
      (node (ref "Q6") (pin "1") (pinfunction "B_1") (pintype "passive"))
      (node (ref "R16") (pin "1") (pinfunction "1_1") (pintype "passive"))
    )
    (net (code "60") (name "Net-(Q7-B)") (class "Default")
      (node (ref "C10") (pin "2") (pinfunction "2_2") (pintype "passive"))
      (node (ref "Q7") (pin "1") (pinfunction "B_1") (pintype "passive"))
      (node (ref "R25") (pin "1") (pinfunction "1_1") (pintype "passive"))
    )
    (net (code "61") (name "Net-(Q8-B)") (class "Default")
      (node (ref "C11") (pin "2") (pinfunction "2_2") (pintype "passive"))
      (node (ref "Q8") (pin "1") (pinfunction "B_1") (pintype "passive"))
      (node (ref "R24") (pin "1") (pinfunction "1_1") (pintype "passive"))
    )
    (net (code "62") (name "Net-(Q9-B)") (class "Default")
      (node (ref "C12") (pin "2") (pinfunction "2_2") (pintype "passive"))
      (node (ref "Q9") (pin "1") (pinfunction "B_1") (pintype "passive"))
      (node (ref "R23") (pin "1") (pinfunction "1_1") (pintype "passive"))
    )
    (net (code "63") (name "Net-(Q10-B)") (class "Default")
      (node (ref "C13") (pin "2") (pinfunction "2_2") (pintype "passive"))
      (node (ref "Q10") (pin "1") (pinfunction "B_1") (pintype "passive"))
      (node (ref "R22") (pin "1") (pinfunction "1_1") (pintype "passive"))
    )
    (net (code "64") (name "Net-(Q11-B)") (class "Default")
      (node (ref "C14") (pin "2") (pinfunction "2_2") (pintype "passive"))
      (node (ref "Q11") (pin "1") (pinfunction "B_1") (pintype "passive"))
      (node (ref "R21") (pin "1") (pinfunction "1_1") (pintype "passive"))
    )
    (net (code "65") (name "Net-(R4-Pad1)") (class "Default")
      (node (ref "R4") (pin "1") (pinfunction "1_1") (pintype "passive"))
      (node (ref "S1") (pin "3") (pinfunction "S_3") (pintype "passive"))
      (node (ref "S1") (pin "4") (pinfunction "S_4") (pintype "passive"))
    )
    (net (code "66") (name "V+") (class "Default")
      (node (ref "C1") (pin "2") (pinfunction "2_2") (pintype "passive"))
      (node (ref "D1") (pin "1") (pinfunction "K_1") (pintype "passive"))
      (node (ref "D2") (pin "1") (pinfunction "C_1") (pintype "passive"))
      (node (ref "D3") (pin "C") (pinfunction "C_C") (pintype "passive"))
      (node (ref "IC1") (pin "3") (pinfunction "VIN_3") (pintype "power_in"))
      (node (ref "IC1") (pin "5") (pinfunction "EN_5") (pintype "input"))
      (node (ref "K1") (pin "1") (pinfunction "COIL1_1") (pintype "passive"))
      (node (ref "X3") (pin "P$1") (pinfunction "KL_P$1") (pintype "passive"))
      (node (ref "X3") (pin "P$2") (pinfunction "KL_P$2") (pintype "passive"))
    )
    (net (code "67") (name "unconnected-(M1-+5V-Pad27)") (class "Default")
      (node (ref "M1") (pin "27") (pinfunction "+5V_27") (pintype "passive"))
    )
    (net (code "68") (name "unconnected-(M1-PA5-Pad22)") (class "Default")
      (node (ref "M1") (pin "22") (pinfunction "PA5_22") (pintype "bidirectional"))
    )
    (net (code "69") (name "unconnected-(M1-PA6-Pad25)") (class "Default")
      (node (ref "M1") (pin "25") (pinfunction "PA6_25") (pintype "bidirectional"))
    )
    (net (code "70") (name "unconnected-(M1-PA11-Pad24)") (class "Default")
      (node (ref "M1") (pin "24") (pinfunction "PA11_24") (pintype "bidirectional"))
    )
    (net (code "71") (name "unconnected-(M1-PA12-Pad23)") (class "Default")
      (node (ref "M1") (pin "23") (pinfunction "PA12_23") (pintype "bidirectional"))
    )
    (net (code "72") (name "unconnected-(M1-PB4-Pad15)") (class "Default")
      (node (ref "M1") (pin "15") (pinfunction "PB4_15") (pintype "bidirectional"))
    )
    (net (code "73") (name "unconnected-(M1-PB5-Pad14)") (class "Default")
      (node (ref "M1") (pin "14") (pinfunction "PB5_14") (pintype "bidirectional"))
    )
    (net (code "74") (name "unconnected-(M1-PB9-Pad13)") (class "Default")
      (node (ref "M1") (pin "13") (pinfunction "PB9_13") (pintype "bidirectional"))
    )
    (net (code "75") (name "unconnected-(M1-~{RST}-Pad3)") (class "Default")
      (node (ref "M1") (pin "3") (pinfunction "~{RST}_3") (pintype "input"))
    )
  )
)
